# FPGA_IO.net
KiCad netlist of a schematic drawn in Altium Designer
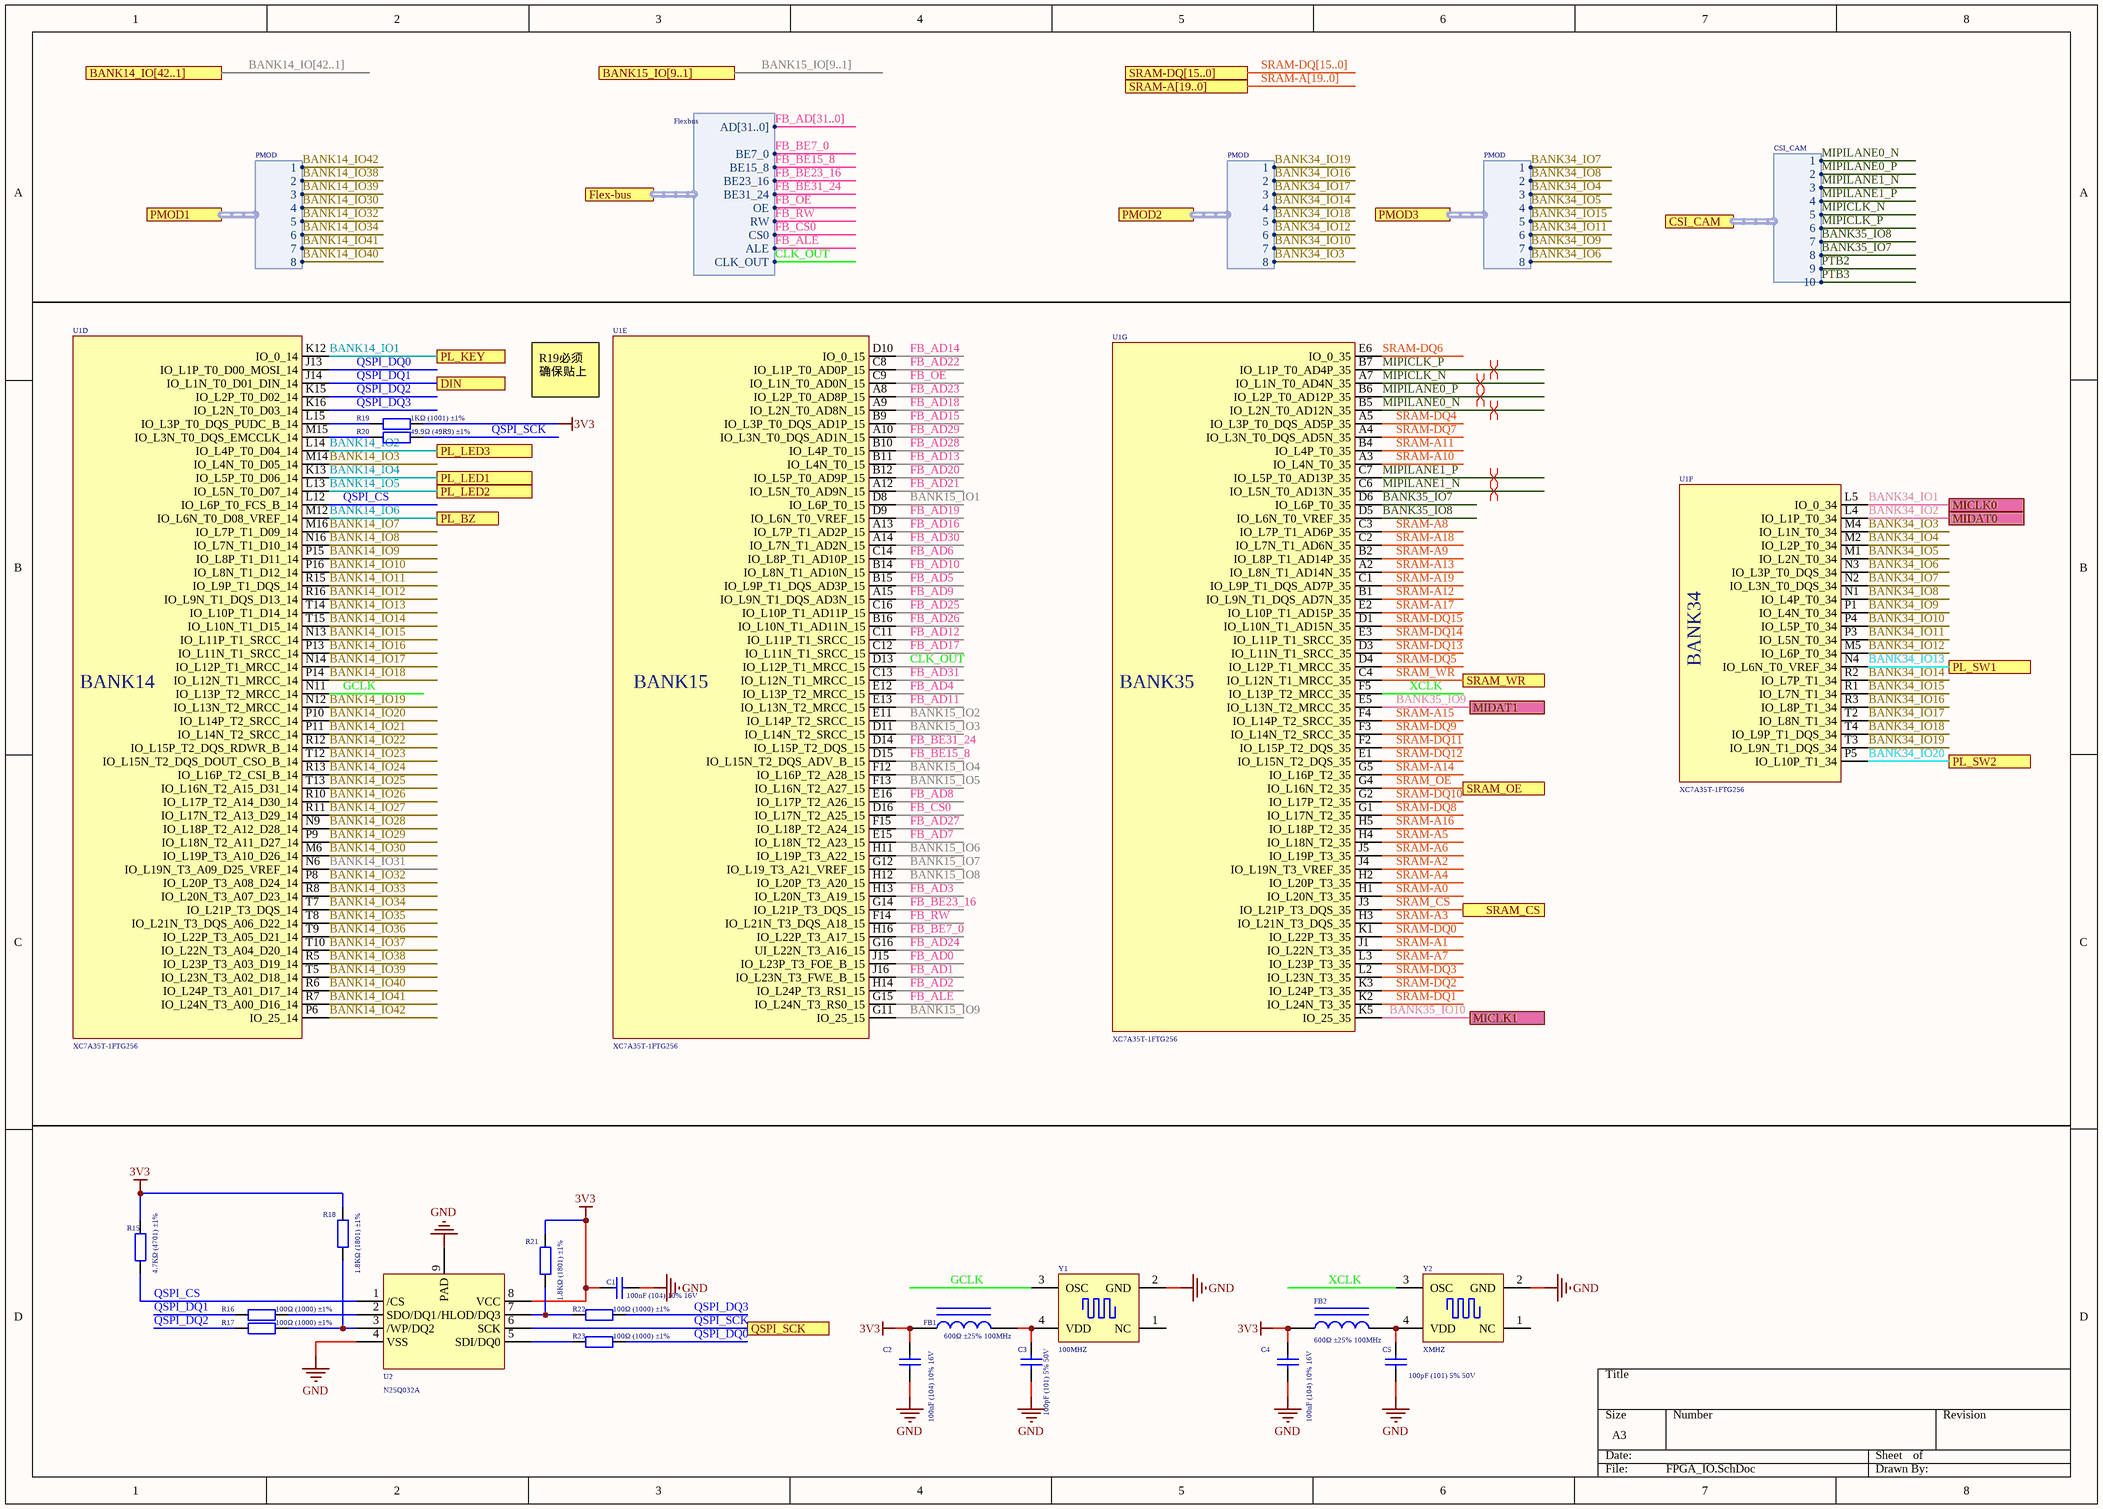
[diagram p0: FPGA_IO.SchDoc]

(export (version "E")
  (design (tool "Eeschema 10.0.6"))
  (components
    (comp (ref "C1")
      (value "100nF (104) 10% 16V")
      (footprint "0402_C")
      (description "贴片电容")
      (libsource (lib "Cap") (part "0402 100nF (104) 10% 16V"))
    )
    (comp (ref "C2")
      (value "100nF (104) 10% 16V")
      (footprint "0402_C")
      (description "贴片电容")
      (libsource (lib "Cap") (part "0402 100nF (104) 10% 16V"))
    )
    (comp (ref "C3")
      (value "100pF (101) 5% 50V")
      (footprint "0402_C")
      (description "贴片电容")
      (libsource (lib "Cap") (part "0402 100pF (101) 5% 50V"))
    )
    (comp (ref "C4")
      (value "100nF (104) 10% 16V")
      (footprint "0402_C")
      (description "贴片电容")
      (libsource (lib "Cap") (part "0402 100nF (104) 10% 16V"))
    )
    (comp (ref "C5")
      (value "100pF (101) 5% 50V")
      (footprint "0402_C")
      (description "贴片电容")
      (libsource (lib "Cap") (part "0402 100pF (101) 5% 50V"))
    )
    (comp (ref "FB1")
      (value "600Ω ±25% 100MHz")
      (footprint "0805_L")
      (description "贴片磁珠")
      (libsource (lib "IUD") (part "0805 600Ω 25% 100MHz"))
    )
    (comp (ref "FB2")
      (value "600Ω ±25% 100MHz")
      (footprint "0805_L")
      (description "贴片磁珠")
      (libsource (lib "IUD") (part "0805 600Ω 25% 100MHz"))
    )
    (comp (ref "R15")
      (value "4.7KΩ (4701) ±1%")
      (footprint "0402_R")
      (description "贴片电阻")
      (libsource (lib "RES") (part "0402 4.7KΩ (4701) 1%"))
    )
    (comp (ref "R16")
      (value "100Ω (1000) ±1%")
      (footprint "0402_R")
      (description "贴片电阻")
      (libsource (lib "RES") (part "0402 100Ω (1000) 1%"))
    )
    (comp (ref "R17")
      (value "100Ω (1000) ±1%")
      (footprint "0402_R")
      (description "贴片电阻")
      (libsource (lib "RES") (part "0402 100Ω (1000) 1%"))
    )
    (comp (ref "R18")
      (value "1.8KΩ (1801) ±1%")
      (footprint "0603_R")
      (description "贴片电阻")
      (libsource (lib "RES") (part "0603 1.8KΩ (1801) 1%"))
    )
    (comp (ref "R19")
      (value "1KΩ (1001) ±1%")
      (footprint "0402_R")
      (description "贴片电阻")
      (libsource (lib "RES") (part "0402 1KΩ (1001) 1%"))
    )
    (comp (ref "R20")
      (value "49.9Ω (49R9) ±1%")
      (footprint "0402_R")
      (description "贴片电阻")
      (libsource (lib "RES") (part "0402 49.9Ω (49R9) 1%"))
    )
    (comp (ref "R21")
      (value "1.8KΩ (1801) ±1%")
      (footprint "0603_R")
      (description "贴片电阻")
      (libsource (lib "RES") (part "0603 1.8KΩ (1801) 1%"))
    )
    (comp (ref "R22")
      (value "100Ω (1000) ±1%")
      (footprint "0402_R")
      (description "贴片电阻")
      (libsource (lib "RES") (part "0402 100Ω (1000) 1%"))
    )
    (comp (ref "R23")
      (value "100Ω (1000) ±1%")
      (footprint "0402_R")
      (description "贴片电阻")
      (libsource (lib "RES") (part "0402 100Ω (1000) 1%"))
    )
    (comp (ref "U1")
      (value "XC7A35T-1FTG256")
      (footprint "BGA100P9X9-81A")
      (libsource (lib "Schlib") (part "XC7A35T-1FTG256"))
    )
    (comp (ref "U2")
      (value "N25Q032A")
      (footprint "QFN127P500X600X100_HS-9N")
      (libsource (lib "2号库") (part "N25Q032A"))
    )
    (comp (ref "Y1") (value "100MHZ") (footprint "XTAL7_3225") (libsource (lib "K60-V4.0") (part "XTAL1")))
    (comp (ref "Y2") (value "XMHZ") (footprint "XTAL7_3225") (libsource (lib "K60-V4.0") (part "XTAL1")))
  )
  (nets
    (net (code "4") (name "/BANK14_IO1") (class "Default")
      (node (ref "U1") (pin "K12") (pinfunction "IO_0_14_K12") (pintype "passive"))
    )
    (net (code "5") (name "/BANK14_IO2") (class "Default")
      (node (ref "U1") (pin "L14") (pinfunction "IO_L4P_T0_D04_14_L14") (pintype "passive"))
    )
    (net (code "6") (name "/BANK14_IO3") (class "Default")
      (node (ref "U1") (pin "M14") (pinfunction "IO_L4N_T0_D05_14_M14") (pintype "passive"))
    )
    (net (code "7") (name "/BANK14_IO4") (class "Default")
      (node (ref "U1") (pin "K13") (pinfunction "IO_L5P_T0_D06_14_K13") (pintype "passive"))
    )
    (net (code "8") (name "/BANK14_IO5") (class "Default")
      (node (ref "U1") (pin "L13") (pinfunction "IO_L5N_T0_D07_14_L13") (pintype "passive"))
    )
    (net (code "9") (name "/BANK14_IO6") (class "Default")
      (node (ref "U1") (pin "M12") (pinfunction "IO_L6N_T0_D08_VREF_14_M12") (pintype "passive"))
    )
    (net (code "10") (name "/BANK14_IO7") (class "Default")
      (node (ref "U1") (pin "M16") (pinfunction "IO_L7P_T1_D09_14_M16") (pintype "passive"))
    )
    (net (code "11") (name "/BANK14_IO8") (class "Default")
      (node (ref "U1") (pin "N16") (pinfunction "IO_L7N_T1_D10_14_N16") (pintype "passive"))
    )
    (net (code "12") (name "/BANK14_IO9") (class "Default")
      (node (ref "U1") (pin "P15") (pinfunction "IO_L8P_T1_D11_14_P15") (pintype "passive"))
    )
    (net (code "13") (name "/BANK14_IO10") (class "Default")
      (node (ref "U1") (pin "P16") (pinfunction "IO_L8N_T1_D12_14_P16") (pintype "passive"))
    )
    (net (code "14") (name "/BANK14_IO11") (class "Default")
      (node (ref "U1") (pin "R15") (pinfunction "IO_L9P_T1_DQS_14_R15") (pintype "passive"))
    )
    (net (code "15") (name "/BANK14_IO12") (class "Default")
      (node (ref "U1") (pin "R16") (pinfunction "IO_L9N_T1_DQS_D13_14_R16") (pintype "passive"))
    )
    (net (code "16") (name "/BANK14_IO13") (class "Default")
      (node (ref "U1") (pin "T14") (pinfunction "IO_L10P_T1_D14_14_T14") (pintype "passive"))
    )
    (net (code "17") (name "/BANK14_IO14") (class "Default")
      (node (ref "U1") (pin "T15") (pinfunction "IO_L10N_T1_D15_14_T15") (pintype "passive"))
    )
    (net (code "18") (name "/BANK14_IO15") (class "Default")
      (node (ref "U1") (pin "N13") (pinfunction "IO_L11P_T1_SRCC_14_N13") (pintype "passive"))
    )
    (net (code "19") (name "/BANK14_IO16") (class "Default")
      (node (ref "U1") (pin "P13") (pinfunction "IO_L11N_T1_SRCC_14_P13") (pintype "passive"))
    )
    (net (code "20") (name "/BANK14_IO17") (class "Default")
      (node (ref "U1") (pin "N14") (pinfunction "IO_L12P_T1_MRCC_14_N14") (pintype "passive"))
    )
    (net (code "21") (name "/BANK14_IO18") (class "Default")
      (node (ref "U1") (pin "P14") (pinfunction "IO_L12N_T1_MRCC_14_P14") (pintype "passive"))
    )
    (net (code "22") (name "/BANK14_IO19") (class "Default")
      (node (ref "U1") (pin "N12") (pinfunction "IO_L13N_T2_MRCC_14_N12") (pintype "passive"))
    )
    (net (code "23") (name "/BANK14_IO20") (class "Default")
      (node (ref "U1") (pin "P10") (pinfunction "IO_L14P_T2_SRCC_14_P10") (pintype "passive"))
    )
    (net (code "24") (name "/BANK14_IO21") (class "Default")
      (node (ref "U1") (pin "P11") (pinfunction "IO_L14N_T2_SRCC_14_P11") (pintype "passive"))
    )
    (net (code "25") (name "/BANK14_IO22") (class "Default")
      (node (ref "U1") (pin "R12") (pinfunction "IO_L15P_T2_DQS_RDWR_B_14_R12") (pintype "passive"))
    )
    (net (code "26") (name "/BANK14_IO23") (class "Default")
      (node (ref "U1") (pin "T12") (pinfunction "IO_L15N_T2_DQS_DOUT_CSO_B_14_T12") (pintype "passive"))
    )
    (net (code "27") (name "/BANK14_IO24") (class "Default")
      (node (ref "U1") (pin "R13") (pinfunction "IO_L16P_T2_CSI_B_14_R13") (pintype "passive"))
    )
    (net (code "28") (name "/BANK14_IO25") (class "Default")
      (node (ref "U1") (pin "T13") (pinfunction "IO_L16N_T2_A15_D31_14_T13") (pintype "passive"))
    )
    (net (code "29") (name "/BANK14_IO26") (class "Default")
      (node (ref "U1") (pin "R10") (pinfunction "IO_L17P_T2_A14_D30_14_R10") (pintype "passive"))
    )
    (net (code "30") (name "/BANK14_IO27") (class "Default")
      (node (ref "U1") (pin "R11") (pinfunction "IO_L17N_T2_A13_D29_14_R11") (pintype "passive"))
    )
    (net (code "31") (name "/BANK14_IO28") (class "Default")
      (node (ref "U1") (pin "N9") (pinfunction "IO_L18P_T2_A12_D28_14_N9") (pintype "passive"))
    )
    (net (code "32") (name "/BANK14_IO29") (class "Default")
      (node (ref "U1") (pin "P9") (pinfunction "IO_L18N_T2_A11_D27_14_P9") (pintype "passive"))
    )
    (net (code "33") (name "/BANK14_IO30") (class "Default")
      (node (ref "U1") (pin "M6") (pinfunction "IO_L19P_T3_A10_D26_14_M6") (pintype "passive"))
    )
    (net (code "34") (name "/BANK14_IO31") (class "Default")
      (node (ref "U1") (pin "N6") (pinfunction "IO_L19N_T3_A09_D25_VREF_14_N6") (pintype "passive"))
    )
    (net (code "35") (name "/BANK14_IO32") (class "Default")
      (node (ref "U1") (pin "P8") (pinfunction "IO_L20P_T3_A08_D24_14_P8") (pintype "passive"))
    )
    (net (code "36") (name "/BANK14_IO33") (class "Default")
      (node (ref "U1") (pin "R8") (pinfunction "IO_L20N_T3_A07_D23_14_R8") (pintype "passive"))
    )
    (net (code "37") (name "/BANK14_IO34") (class "Default")
      (node (ref "U1") (pin "T7") (pinfunction "IO_L21P_T3_DQS_14_T7") (pintype "passive"))
    )
    (net (code "38") (name "/BANK14_IO35") (class "Default")
      (node (ref "U1") (pin "T8") (pinfunction "IO_L21N_T3_DQS_A06_D22_14_T8") (pintype "passive"))
    )
    (net (code "39") (name "/BANK14_IO36") (class "Default")
      (node (ref "U1") (pin "T9") (pinfunction "IO_L22P_T3_A05_D21_14_T9") (pintype "passive"))
    )
    (net (code "40") (name "/BANK14_IO37") (class "Default")
      (node (ref "U1") (pin "T10") (pinfunction "IO_L22N_T3_A04_D20_14_T10") (pintype "passive"))
    )
    (net (code "41") (name "/BANK14_IO38") (class "Default")
      (node (ref "U1") (pin "R5") (pinfunction "IO_L23P_T3_A03_D19_14_R5") (pintype "passive"))
    )
    (net (code "42") (name "/BANK14_IO39") (class "Default")
      (node (ref "U1") (pin "T5") (pinfunction "IO_L23N_T3_A02_D18_14_T5") (pintype "passive"))
    )
    (net (code "43") (name "/BANK14_IO40") (class "Default")
      (node (ref "U1") (pin "R6") (pinfunction "IO_L24P_T3_A01_D17_14_R6") (pintype "passive"))
    )
    (net (code "44") (name "/BANK14_IO41") (class "Default")
      (node (ref "U1") (pin "R7") (pinfunction "IO_L24N_T3_A00_D16_14_R7") (pintype "passive"))
    )
    (net (code "45") (name "/BANK14_IO42") (class "Default")
      (node (ref "U1") (pin "P6") (pinfunction "IO_25_14_P6") (pintype "passive"))
    )
    (net (code "47") (name "/BANK15_IO1") (class "Default")
      (node (ref "U1") (pin "D8") (pinfunction "IO_L6P_T0_15_D8") (pintype "passive"))
    )
    (net (code "48") (name "/BANK15_IO2") (class "Default")
      (node (ref "U1") (pin "E11") (pinfunction "IO_L14P_T2_SRCC_15_E11") (pintype "passive"))
    )
    (net (code "49") (name "/BANK15_IO3") (class "Default")
      (node (ref "U1") (pin "D11") (pinfunction "IO_L14N_T2_SRCC_15_D11") (pintype "passive"))
    )
    (net (code "50") (name "/BANK15_IO4") (class "Default")
      (node (ref "U1") (pin "F12") (pinfunction "IO_L16P_T2_A28_15_F12") (pintype "passive"))
    )
    (net (code "51") (name "/BANK15_IO5") (class "Default")
      (node (ref "U1") (pin "F13") (pinfunction "IO_L16N_T2_A27_15_F13") (pintype "passive"))
    )
    (net (code "52") (name "/BANK15_IO6") (class "Default")
      (node (ref "U1") (pin "H11") (pinfunction "IO_L19P_T3_A22_15_H11") (pintype "passive"))
    )
    (net (code "53") (name "/BANK15_IO7") (class "Default")
      (node (ref "U1") (pin "G12") (pinfunction "IO_L19_T3_A21_VREF_15_G12") (pintype "passive"))
    )
    (net (code "54") (name "/BANK15_IO8") (class "Default")
      (node (ref "U1") (pin "H12") (pinfunction "IO_L20P_T3_A20_15_H12") (pintype "passive"))
    )
    (net (code "55") (name "/BANK15_IO9") (class "Default")
      (node (ref "U1") (pin "G11") (pinfunction "IO_25_15_G11") (pintype "passive"))
    )
    (net (code "57") (name "/BANK34_IO1") (class "Default")
      (node (ref "U1") (pin "L5") (pinfunction "IO_0_34_L5") (pintype "passive"))
    )
    (net (code "58") (name "/BANK34_IO2") (class "Default")
      (node (ref "U1") (pin "L4") (pinfunction "IO_L1P_T0_34_L4") (pintype "passive"))
    )
    (net (code "59") (name "/BANK34_IO3") (class "Default")
      (node (ref "U1") (pin "M4") (pinfunction "IO_L1N_T0_34_M4") (pintype "passive"))
    )
    (net (code "60") (name "/BANK34_IO4") (class "Default")
      (node (ref "U1") (pin "M2") (pinfunction "IO_L2P_T0_34_M2") (pintype "passive"))
    )
    (net (code "61") (name "/BANK34_IO5") (class "Default")
      (node (ref "U1") (pin "M1") (pinfunction "IO_L2N_T0_34_M1") (pintype "passive"))
    )
    (net (code "62") (name "/BANK34_IO6") (class "Default")
      (node (ref "U1") (pin "N3") (pinfunction "IO_L3P_T0_DQS_34_N3") (pintype "passive"))
    )
    (net (code "63") (name "/BANK34_IO7") (class "Default")
      (node (ref "U1") (pin "N2") (pinfunction "IO_L3N_T0_DQS_34_N2") (pintype "passive"))
    )
    (net (code "64") (name "/BANK34_IO8") (class "Default")
      (node (ref "U1") (pin "N1") (pinfunction "IO_L4P_T0_34_N1") (pintype "passive"))
    )
    (net (code "65") (name "/BANK34_IO9") (class "Default")
      (node (ref "U1") (pin "P1") (pinfunction "IO_L4N_T0_34_P1") (pintype "passive"))
    )
    (net (code "66") (name "/BANK34_IO10") (class "Default")
      (node (ref "U1") (pin "P4") (pinfunction "IO_L5P_T0_34_P4") (pintype "passive"))
    )
    (net (code "67") (name "/BANK34_IO11") (class "Default")
      (node (ref "U1") (pin "P3") (pinfunction "IO_L5N_T0_34_P3") (pintype "passive"))
    )
    (net (code "68") (name "/BANK34_IO12") (class "Default")
      (node (ref "U1") (pin "M5") (pinfunction "IO_L6P_T0_34_M5") (pintype "passive"))
    )
    (net (code "69") (name "/BANK34_IO13") (class "Default")
      (node (ref "U1") (pin "N4") (pinfunction "IO_L6N_T0_VREF_34_N4") (pintype "passive"))
    )
    (net (code "70") (name "/BANK34_IO14") (class "Default")
      (node (ref "U1") (pin "R2") (pinfunction "IO_L7P_T1_34_R2") (pintype "passive"))
    )
    (net (code "71") (name "/BANK34_IO15") (class "Default")
      (node (ref "U1") (pin "R1") (pinfunction "IO_L7N_T1_34_R1") (pintype "passive"))
    )
    (net (code "72") (name "/BANK34_IO16") (class "Default")
      (node (ref "U1") (pin "R3") (pinfunction "IO_L8P_T1_34_R3") (pintype "passive"))
    )
    (net (code "73") (name "/BANK34_IO17") (class "Default")
      (node (ref "U1") (pin "T2") (pinfunction "IO_L8N_T1_34_T2") (pintype "passive"))
    )
    (net (code "74") (name "/BANK34_IO18") (class "Default")
      (node (ref "U1") (pin "T4") (pinfunction "IO_L9P_T1_DQS_34_T4") (pintype "passive"))
    )
    (net (code "75") (name "/BANK34_IO19") (class "Default")
      (node (ref "U1") (pin "T3") (pinfunction "IO_L9N_T1_DQS_34_T3") (pintype "passive"))
    )
    (net (code "76") (name "/BANK34_IO20") (class "Default")
      (node (ref "U1") (pin "P5") (pinfunction "IO_L10P_T1_34_P5") (pintype "passive"))
    )
    (net (code "77") (name "/BANK35_IO7") (class "Default")
      (node (ref "U1") (pin "D6") (pinfunction "IO_L6P_T0_35_D6") (pintype "passive"))
    )
    (net (code "78") (name "/BANK35_IO8") (class "Default")
      (node (ref "U1") (pin "D5") (pinfunction "IO_L6N_T0_VREF_35_D5") (pintype "passive"))
    )
    (net (code "79") (name "/BANK35_IO9") (class "Default")
      (node (ref "U1") (pin "E5") (pinfunction "IO_L13N_T2_MRCC_35_E5") (pintype "passive"))
    )
    (net (code "80") (name "/BANK35_IO10") (class "Default")
      (node (ref "U1") (pin "K5") (pinfunction "IO_25_35_K5") (pintype "passive"))
    )
    (net (code "81") (name "/CLK_OUT") (class "Default")
      (node (ref "U1") (pin "D13") (pinfunction "IO_L12P_T1_MRCC_15_D13") (pintype "passive"))
    )
    (net (code "82") (name "/FB_AD0") (class "Default")
      (node (ref "U1") (pin "J15") (pinfunction "IO_L23P_T3_FOE_B_15_J15") (pintype "passive"))
    )
    (net (code "83") (name "/FB_AD1") (class "Default")
      (node (ref "U1") (pin "J16") (pinfunction "IO_L23N_T3_FWE_B_15_J16") (pintype "passive"))
    )
    (net (code "84") (name "/FB_AD2") (class "Default")
      (node (ref "U1") (pin "H14") (pinfunction "IO_L24P_T3_RS1_15_H14") (pintype "passive"))
    )
    (net (code "85") (name "/FB_AD3") (class "Default")
      (node (ref "U1") (pin "H13") (pinfunction "IO_L20N_T3_A19_15_H13") (pintype "passive"))
    )
    (net (code "86") (name "/FB_AD4") (class "Default")
      (node (ref "U1") (pin "E12") (pinfunction "IO_L13P_T2_MRCC_15_E12") (pintype "passive"))
    )
    (net (code "87") (name "/FB_AD5") (class "Default")
      (node (ref "U1") (pin "B15") (pinfunction "IO_L9P_T1_DQS_AD3P_15_B15") (pintype "passive"))
    )
    (net (code "88") (name "/FB_AD6") (class "Default")
      (node (ref "U1") (pin "C14") (pinfunction "IO_L8P_T1_AD10P_15_C14") (pintype "passive"))
    )
    (net (code "89") (name "/FB_AD7") (class "Default")
      (node (ref "U1") (pin "E15") (pinfunction "IO_L18N_T2_A23_15_E15") (pintype "passive"))
    )
    (net (code "90") (name "/FB_AD8") (class "Default")
      (node (ref "U1") (pin "E16") (pinfunction "IO_L17P_T2_A26_15_E16") (pintype "passive"))
    )
    (net (code "91") (name "/FB_AD9") (class "Default")
      (node (ref "U1") (pin "A15") (pinfunction "IO_L9N_T1_DQS_AD3N_15_A15") (pintype "passive"))
    )
    (net (code "92") (name "/FB_AD10") (class "Default")
      (node (ref "U1") (pin "B14") (pinfunction "IO_L8N_T1_AD10N_15_B14") (pintype "passive"))
    )
    (net (code "93") (name "/FB_AD11") (class "Default")
      (node (ref "U1") (pin "E13") (pinfunction "IO_L13N_T2_MRCC_15_E13") (pintype "passive"))
    )
    (net (code "94") (name "/FB_AD12") (class "Default")
      (node (ref "U1") (pin "C11") (pinfunction "IO_L11P_T1_SRCC_15_C11") (pintype "passive"))
    )
    (net (code "95") (name "/FB_AD13") (class "Default")
      (node (ref "U1") (pin "B11") (pinfunction "IO_L4N_T0_15_B11") (pintype "passive"))
    )
    (net (code "96") (name "/FB_AD14") (class "Default")
      (node (ref "U1") (pin "D10") (pinfunction "IO_0_15_D10") (pintype "passive"))
    )
    (net (code "97") (name "/FB_AD15") (class "Default")
      (node (ref "U1") (pin "B9") (pinfunction "IO_L3P_T0_DQS_AD1P_15_B9") (pintype "passive"))
    )
    (net (code "98") (name "/FB_AD16") (class "Default")
      (node (ref "U1") (pin "A13") (pinfunction "IO_L7P_T1_AD2P_15_A13") (pintype "passive"))
    )
    (net (code "99") (name "/FB_AD17") (class "Default")
      (node (ref "U1") (pin "C12") (pinfunction "IO_L11N_T1_SRCC_15_C12") (pintype "passive"))
    )
    (net (code "100") (name "/FB_AD18") (class "Default")
      (node (ref "U1") (pin "A9") (pinfunction "IO_L2N_T0_AD8N_15_A9") (pintype "passive"))
    )
    (net (code "101") (name "/FB_AD19") (class "Default")
      (node (ref "U1") (pin "D9") (pinfunction "IO_L6N_T0_VREF_15_D9") (pintype "passive"))
    )
    (net (code "102") (name "/FB_AD20") (class "Default")
      (node (ref "U1") (pin "B12") (pinfunction "IO_L5P_T0_AD9P_15_B12") (pintype "passive"))
    )
    (net (code "103") (name "/FB_AD21") (class "Default")
      (node (ref "U1") (pin "A12") (pinfunction "IO_L5N_T0_AD9N_15_A12") (pintype "passive"))
    )
    (net (code "104") (name "/FB_AD22") (class "Default")
      (node (ref "U1") (pin "C8") (pinfunction "IO_L1P_T0_AD0P_15_C8") (pintype "passive"))
    )
    (net (code "105") (name "/FB_AD23") (class "Default")
      (node (ref "U1") (pin "A8") (pinfunction "IO_L2P_T0_AD8P_15_A8") (pintype "passive"))
    )
    (net (code "106") (name "/FB_AD24") (class "Default")
      (node (ref "U1") (pin "G16") (pinfunction "UI_L22N_T3_A16_15_G16") (pintype "passive"))
    )
    (net (code "107") (name "/FB_AD25") (class "Default")
      (node (ref "U1") (pin "C16") (pinfunction "IO_L10P_T1_AD11P_15_C16") (pintype "passive"))
    )
    (net (code "108") (name "/FB_AD26") (class "Default")
      (node (ref "U1") (pin "B16") (pinfunction "IO_L10N_T1_AD11N_15_B16") (pintype "passive"))
    )
    (net (code "109") (name "/FB_AD27") (class "Default")
      (node (ref "U1") (pin "F15") (pinfunction "IO_L18P_T2_A24_15_F15") (pintype "passive"))
    )
    (net (code "110") (name "/FB_AD28") (class "Default")
      (node (ref "U1") (pin "B10") (pinfunction "IO_L4P_T0_15_B10") (pintype "passive"))
    )
    (net (code "111") (name "/FB_AD29") (class "Default")
      (node (ref "U1") (pin "A10") (pinfunction "IO_L3N_T0_DQS_AD1N_15_A10") (pintype "passive"))
    )
    (net (code "112") (name "/FB_AD30") (class "Default")
      (node (ref "U1") (pin "A14") (pinfunction "IO_L7N_T1_AD2N_15_A14") (pintype "passive"))
    )
    (net (code "113") (name "/FB_AD31") (class "Default")
      (node (ref "U1") (pin "C13") (pinfunction "IO_L12N_T1_MRCC_15_C13") (pintype "passive"))
    )
    (net (code "115") (name "/FB_ALE") (class "Default")
      (node (ref "U1") (pin "G15") (pinfunction "IO_L24N_T3_RS0_15_G15") (pintype "passive"))
    )
    (net (code "116") (name "/FB_BE7_0") (class "Default")
      (node (ref "U1") (pin "H16") (pinfunction "IO_L22P_T3_A17_15_H16") (pintype "passive"))
    )
    (net (code "117") (name "/FB_BE15_8") (class "Default")
      (node (ref "U1") (pin "D15") (pinfunction "IO_L15N_T2_DQS_ADV_B_15_D15") (pintype "passive"))
    )
    (net (code "118") (name "/FB_BE23_16") (class "Default")
      (node (ref "U1") (pin "G14") (pinfunction "IO_L21P_T3_DQS_15_G14") (pintype "passive"))
    )
    (net (code "119") (name "/FB_BE31_24") (class "Default")
      (node (ref "U1") (pin "D14") (pinfunction "IO_L15P_T2_DQS_15_D14") (pintype "passive"))
    )
    (net (code "120") (name "/FB_CS0") (class "Default")
      (node (ref "U1") (pin "D16") (pinfunction "IO_L17N_T2_A25_15_D16") (pintype "passive"))
    )
    (net (code "121") (name "/FB_OE") (class "Default")
      (node (ref "U1") (pin "C9") (pinfunction "IO_L1N_T0_AD0N_15_C9") (pintype "passive"))
    )
    (net (code "122") (name "/FB_RW") (class "Default")
      (node (ref "U1") (pin "F14") (pinfunction "IO_L21N_T3_DQS_A18_15_F14") (pintype "passive"))
    )
    (net (code "123") (name "/GCLK") (class "Default")
      (node (ref "U1") (pin "N11") (pinfunction "IO_L13P_T2_MRCC_14_N11") (pintype "passive"))
      (node (ref "Y1") (pin "3") (pinfunction "OSC_3") (pintype "passive"))
    )
    (net (code "124") (name "/MIPICLK_N") (class "Default")
      (node (ref "U1") (pin "A7") (pinfunction "IO_L1N_T0_AD4N_35_A7") (pintype "passive"))
    )
    (net (code "125") (name "/MIPICLK_P") (class "Default")
      (node (ref "U1") (pin "B7") (pinfunction "IO_L1P_T0_AD4P_35_B7") (pintype "passive"))
    )
    (net (code "126") (name "/MIPILANE0_N") (class "Default")
      (node (ref "U1") (pin "B5") (pinfunction "IO_L2N_T0_AD12N_35_B5") (pintype "passive"))
    )
    (net (code "127") (name "/MIPILANE0_P") (class "Default")
      (node (ref "U1") (pin "B6") (pinfunction "IO_L2P_T0_AD12P_35_B6") (pintype "passive"))
    )
    (net (code "128") (name "/MIPILANE1_N") (class "Default")
      (node (ref "U1") (pin "C6") (pinfunction "IO_L5N_T0_AD13N_35_C6") (pintype "passive"))
    )
    (net (code "129") (name "/MIPILANE1_P") (class "Default")
      (node (ref "U1") (pin "C7") (pinfunction "IO_L5P_T0_AD13P_35_C7") (pintype "passive"))
    )
    (net (code "132") (name "/QSPI_CS") (class "Default")
      (node (ref "R15") (pin "1") (pinfunction "1_1") (pintype "passive"))
      (node (ref "U1") (pin "L12") (pinfunction "IO_L6P_T0_FCS_B_14_L12") (pintype "passive"))
      (node (ref "U2") (pin "1") (pinfunction "/CS_1") (pintype "passive"))
    )
    (net (code "133") (name "/QSPI_DQ0") (class "Default")
      (node (ref "R23") (pin "2") (pinfunction "2_2") (pintype "passive"))
      (node (ref "U1") (pin "J13") (pinfunction "IO_L1P_T0_D00_MOSI_14_J13") (pintype "passive"))
    )
    (net (code "134") (name "/QSPI_DQ1") (class "Default")
      (node (ref "R16") (pin "1") (pinfunction "1_1") (pintype "passive"))
      (node (ref "U1") (pin "J14") (pinfunction "IO_L1N_T0_D01_DIN_14_J14") (pintype "passive"))
    )
    (net (code "135") (name "/QSPI_DQ2") (class "Default")
      (node (ref "R17") (pin "1") (pinfunction "1_1") (pintype "passive"))
      (node (ref "U1") (pin "K15") (pinfunction "IO_L2P_T0_D02_14_K15") (pintype "passive"))
    )
    (net (code "136") (name "/QSPI_DQ3") (class "Default")
      (node (ref "R22") (pin "2") (pinfunction "2_2") (pintype "passive"))
      (node (ref "U1") (pin "K16") (pinfunction "IO_L2N_T0_D03_14_K16") (pintype "passive"))
    )
    (net (code "137") (name "/QSPI_SCK") (class "Default")
      (node (ref "R20") (pin "2") (pinfunction "2_2") (pintype "passive"))
      (node (ref "U2") (pin "6") (pinfunction "SCK_6") (pintype "passive"))
    )
    (net (code "138") (name "/SRAM-A0") (class "Default")
      (node (ref "U1") (pin "H1") (pinfunction "IO_L20N_T3_35_H1") (pintype "passive"))
    )
    (net (code "139") (name "/SRAM-A1") (class "Default")
      (node (ref "U1") (pin "J1") (pinfunction "IO_L22N_T3_35_J1") (pintype "passive"))
    )
    (net (code "140") (name "/SRAM-A2") (class "Default")
      (node (ref "U1") (pin "J4") (pinfunction "IO_L19N_T3_VREF_35_J4") (pintype "passive"))
    )
    (net (code "141") (name "/SRAM-A3") (class "Default")
      (node (ref "U1") (pin "H3") (pinfunction "IO_L21N_T3_DQS_35_H3") (pintype "passive"))
    )
    (net (code "142") (name "/SRAM-A4") (class "Default")
      (node (ref "U1") (pin "H2") (pinfunction "IO_L20P_T3_35_H2") (pintype "passive"))
    )
    (net (code "143") (name "/SRAM-A5") (class "Default")
      (node (ref "U1") (pin "H4") (pinfunction "IO_L18N_T2_35_H4") (pintype "passive"))
    )
    (net (code "144") (name "/SRAM-A6") (class "Default")
      (node (ref "U1") (pin "J5") (pinfunction "IO_L19P_T3_35_J5") (pintype "passive"))
    )
    (net (code "145") (name "/SRAM-A7") (class "Default")
      (node (ref "U1") (pin "L3") (pinfunction "IO_L23P_T3_35_L3") (pintype "passive"))
    )
    (net (code "146") (name "/SRAM-A8") (class "Default")
      (node (ref "U1") (pin "C3") (pinfunction "IO_L7P_T1_AD6P_35_C3") (pintype "passive"))
    )
    (net (code "147") (name "/SRAM-A9") (class "Default")
      (node (ref "U1") (pin "B2") (pinfunction "IO_L8P_T1_AD14P_35_B2") (pintype "passive"))
    )
    (net (code "148") (name "/SRAM-A10") (class "Default")
      (node (ref "U1") (pin "A3") (pinfunction "IO_L4N_T0_35_A3") (pintype "passive"))
    )
    (net (code "149") (name "/SRAM-A11") (class "Default")
      (node (ref "U1") (pin "B4") (pinfunction "IO_L4P_T0_35_B4") (pintype "passive"))
    )
    (net (code "150") (name "/SRAM-A12") (class "Default")
      (node (ref "U1") (pin "B1") (pinfunction "IO_L9N_T1_DQS_AD7N_35_B1") (pintype "passive"))
    )
    (net (code "151") (name "/SRAM-A13") (class "Default")
      (node (ref "U1") (pin "A2") (pinfunction "IO_L8N_T1_AD14N_35_A2") (pintype "passive"))
    )
    (net (code "152") (name "/SRAM-A14") (class "Default")
      (node (ref "U1") (pin "G5") (pinfunction "IO_L16P_T2_35_G5") (pintype "passive"))
    )
    (net (code "153") (name "/SRAM-A15") (class "Default")
      (node (ref "U1") (pin "F4") (pinfunction "IO_L14P_T2_SRCC_35_F4") (pintype "passive"))
    )
    (net (code "154") (name "/SRAM-A16") (class "Default")
      (node (ref "U1") (pin "H5") (pinfunction "IO_L18P_T2_35_H5") (pintype "passive"))
    )
    (net (code "155") (name "/SRAM-A17") (class "Default")
      (node (ref "U1") (pin "E2") (pinfunction "IO_L10P_T1_AD15P_35_E2") (pintype "passive"))
    )
    (net (code "156") (name "/SRAM-A18") (class "Default")
      (node (ref "U1") (pin "C2") (pinfunction "IO_L7N_T1_AD6N_35_C2") (pintype "passive"))
    )
    (net (code "157") (name "/SRAM-A19") (class "Default")
      (node (ref "U1") (pin "C1") (pinfunction "IO_L9P_T1_DQS_AD7P_35_C1") (pintype "passive"))
    )
    (net (code "159") (name "/SRAM-DQ0") (class "Default")
      (node (ref "U1") (pin "K1") (pinfunction "IO_L22P_T3_35_K1") (pintype "passive"))
    )
    (net (code "160") (name "/SRAM-DQ1") (class "Default")
      (node (ref "U1") (pin "K2") (pinfunction "IO_L24N_T3_35_K2") (pintype "passive"))
    )
    (net (code "161") (name "/SRAM-DQ2") (class "Default")
      (node (ref "U1") (pin "K3") (pinfunction "IO_L24P_T3_35_K3") (pintype "passive"))
    )
    (net (code "162") (name "/SRAM-DQ3") (class "Default")
      (node (ref "U1") (pin "L2") (pinfunction "IO_L23N_T3_35_L2") (pintype "passive"))
    )
    (net (code "163") (name "/SRAM-DQ4") (class "Default")
      (node (ref "U1") (pin "A5") (pinfunction "IO_L3P_T0_DQS_AD5P_35_A5") (pintype "passive"))
    )
    (net (code "164") (name "/SRAM-DQ5") (class "Default")
      (node (ref "U1") (pin "D4") (pinfunction "IO_L12P_T1_MRCC_35_D4") (pintype "passive"))
    )
    (net (code "165") (name "/SRAM-DQ6") (class "Default")
      (node (ref "U1") (pin "E6") (pinfunction "IO_0_35_E6") (pintype "passive"))
    )
    (net (code "166") (name "/SRAM-DQ7") (class "Default")
      (node (ref "U1") (pin "A4") (pinfunction "IO_L3N_T0_DQS_AD5N_35_A4") (pintype "passive"))
    )
    (net (code "167") (name "/SRAM-DQ8") (class "Default")
      (node (ref "U1") (pin "G1") (pinfunction "IO_L17N_T2_35_G1") (pintype "passive"))
    )
    (net (code "168") (name "/SRAM-DQ9") (class "Default")
      (node (ref "U1") (pin "F3") (pinfunction "IO_L14N_T2_SRCC_35_F3") (pintype "passive"))
    )
    (net (code "169") (name "/SRAM-DQ10") (class "Default")
      (node (ref "U1") (pin "G2") (pinfunction "IO_L17P_T2_35_G2") (pintype "passive"))
    )
    (net (code "170") (name "/SRAM-DQ11") (class "Default")
      (node (ref "U1") (pin "F2") (pinfunction "IO_L15P_T2_DQS_35_F2") (pintype "passive"))
    )
    (net (code "171") (name "/SRAM-DQ12") (class "Default")
      (node (ref "U1") (pin "E1") (pinfunction "IO_L15N_T2_DQS_35_E1") (pintype "passive"))
    )
    (net (code "172") (name "/SRAM-DQ13") (class "Default")
      (node (ref "U1") (pin "D3") (pinfunction "IO_L11N_T1_SRCC_35_D3") (pintype "passive"))
    )
    (net (code "173") (name "/SRAM-DQ14") (class "Default")
      (node (ref "U1") (pin "E3") (pinfunction "IO_L11P_T1_SRCC_35_E3") (pintype "passive"))
    )
    (net (code "174") (name "/SRAM-DQ15") (class "Default")
      (node (ref "U1") (pin "D1") (pinfunction "IO_L10N_T1_AD15N_35_D1") (pintype "passive"))
    )
    (net (code "176") (name "/SRAM_CS") (class "Default")
      (node (ref "U1") (pin "J3") (pinfunction "IO_L21P_T3_DQS_35_J3") (pintype "passive"))
    )
    (net (code "177") (name "/SRAM_OE") (class "Default")
      (node (ref "U1") (pin "G4") (pinfunction "IO_L16N_T2_35_G4") (pintype "passive"))
    )
    (net (code "178") (name "/SRAM_WR") (class "Default")
      (node (ref "U1") (pin "C4") (pinfunction "IO_L12N_T1_MRCC_35_C4") (pintype "passive"))
    )
    (net (code "179") (name "/XCLK") (class "Default")
      (node (ref "U1") (pin "F5") (pinfunction "IO_L13P_T2_MRCC_35_F5") (pintype "passive"))
      (node (ref "Y2") (pin "3") (pinfunction "OSC_3") (pintype "passive"))
    )
    (net (code "183") (name "3V3") (class "Default")
      (node (ref "C1") (pin "1") (pinfunction "1_1") (pintype "passive"))
      (node (ref "C2") (pin "2") (pinfunction "2_2") (pintype "passive"))
      (node (ref "C4") (pin "2") (pinfunction "2_2") (pintype "passive"))
      (node (ref "FB1") (pin "1") (pinfunction "1_1") (pintype "passive"))
      (node (ref "FB2") (pin "1") (pinfunction "1_1") (pintype "passive"))
      (node (ref "R15") (pin "2") (pinfunction "2_2") (pintype "passive"))
      (node (ref "R18") (pin "2") (pinfunction "2_2") (pintype "passive"))
      (node (ref "R19") (pin "2") (pinfunction "2_2") (pintype "passive"))
      (node (ref "R21") (pin "2") (pinfunction "2_2") (pintype "passive"))
      (node (ref "U2") (pin "8") (pinfunction "VCC_8") (pintype "passive"))
    )
    (net (code "184") (name "GND") (class "Default")
      (node (ref "C1") (pin "2") (pinfunction "2_2") (pintype "passive"))
      (node (ref "C2") (pin "1") (pinfunction "1_1") (pintype "passive"))
      (node (ref "C3") (pin "1") (pinfunction "1_1") (pintype "passive"))
      (node (ref "C4") (pin "1") (pinfunction "1_1") (pintype "passive"))
      (node (ref "C5") (pin "1") (pinfunction "1_1") (pintype "passive"))
      (node (ref "U2") (pin "4") (pinfunction "VSS_4") (pintype "passive"))
      (node (ref "U2") (pin "9") (pinfunction "PAD_9") (pintype "passive"))
      (node (ref "Y1") (pin "2") (pinfunction "GND_2") (pintype "passive"))
      (node (ref "Y2") (pin "2") (pinfunction "GND_2") (pintype "passive"))
    )
    (net (code "185") (name "Net-(U1D-IO_L3N_T0_DQS_EMCCLK_14)") (class "Default")
      (node (ref "R20") (pin "1") (pinfunction "1_1") (pintype "passive"))
      (node (ref "U1") (pin "M15") (pinfunction "IO_L3N_T0_DQS_EMCCLK_14_M15") (pintype "passive"))
    )
    (net (code "186") (name "Net-(U1D-IO_L3P_T0_DQS_PUDC_B_14)") (class "Default")
      (node (ref "R19") (pin "1") (pinfunction "1_1") (pintype "passive"))
      (node (ref "U1") (pin "L15") (pinfunction "IO_L3P_T0_DQS_PUDC_B_14_L15") (pintype "passive"))
    )
    (net (code "187") (name "Net-(U2-SDI{slash}DQ0)") (class "Default")
      (node (ref "R23") (pin "1") (pinfunction "1_1") (pintype "passive"))
      (node (ref "U2") (pin "5") (pinfunction "SDI/DQ0_5") (pintype "passive"))
    )
    (net (code "188") (name "Net-(U2-SDO{slash}DQ1)") (class "Default")
      (node (ref "R16") (pin "2") (pinfunction "2_2") (pintype "passive"))
      (node (ref "U2") (pin "2") (pinfunction "SDO/DQ1_2") (pintype "passive"))
    )
    (net (code "189") (name "Net-(U2-{slash}HLOD{slash}DQ3)") (class "Default")
      (node (ref "R21") (pin "1") (pinfunction "1_1") (pintype "passive"))
      (node (ref "R22") (pin "1") (pinfunction "1_1") (pintype "passive"))
      (node (ref "U2") (pin "7") (pinfunction "/HLOD/DQ3_7") (pintype "passive"))
    )
    (net (code "190") (name "Net-(U2-{slash}WP{slash}DQ2)") (class "Default")
      (node (ref "R17") (pin "2") (pinfunction "2_2") (pintype "passive"))
      (node (ref "R18") (pin "1") (pinfunction "1_1") (pintype "passive"))
      (node (ref "U2") (pin "3") (pinfunction "/WP/DQ2_3") (pintype "passive"))
    )
    (net (code "191") (name "Net-(Y1-VDD)") (class "Default")
      (node (ref "C3") (pin "2") (pinfunction "2_2") (pintype "passive"))
      (node (ref "FB1") (pin "2") (pinfunction "2_2") (pintype "passive"))
      (node (ref "Y1") (pin "4") (pinfunction "VDD_4") (pintype "passive"))
    )
    (net (code "192") (name "Net-(Y2-VDD)") (class "Default")
      (node (ref "C5") (pin "2") (pinfunction "2_2") (pintype "passive"))
      (node (ref "FB2") (pin "2") (pinfunction "2_2") (pintype "passive"))
      (node (ref "Y2") (pin "4") (pinfunction "VDD_4") (pintype "passive"))
    )
    (net (code "193") (name "unconnected-(Y1-NC-Pad1)") (class "Default")
      (node (ref "Y1") (pin "1") (pinfunction "NC_1") (pintype "passive"))
    )
    (net (code "194") (name "unconnected-(Y2-NC-Pad1)") (class "Default")
      (node (ref "Y2") (pin "1") (pinfunction "NC_1") (pintype "passive"))
    )
  )
)
